# main.net
KiCad netlist of a schematic drawn in Altium Designer
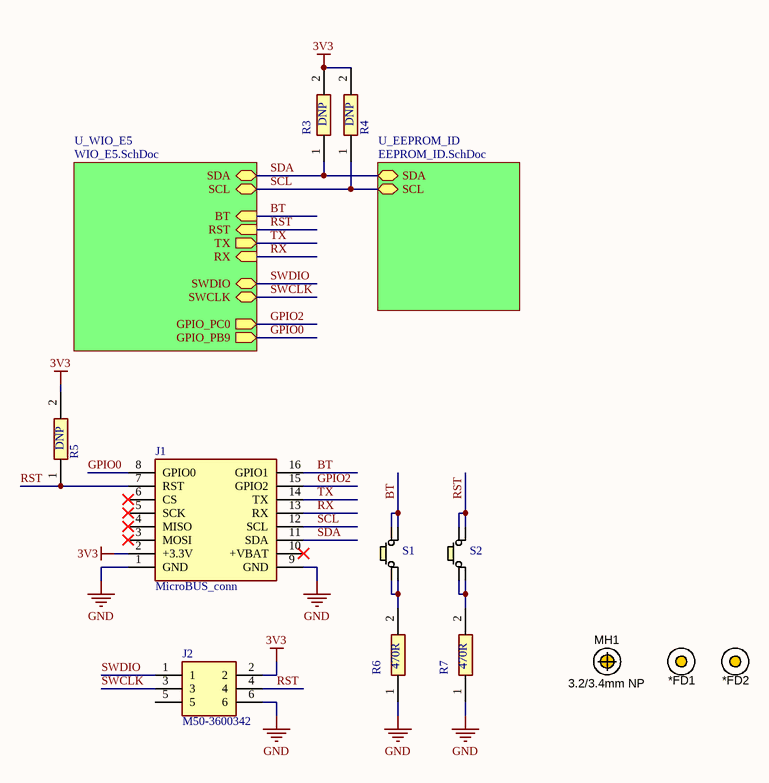
[diagram p0: main.SchDoc]

(export (version "E")
  (design (tool "Eeschema 10.0.6"))
  (components
    (comp (ref "*FD1")
      (value "FIDUCIAL")
      (footprint "IntLibGenerator:FIDUCIAL")
      (description "Fiducial")
      (fields
        (field (name "PARTNUMBER") "MCH_00028")
        (field (name "MANUFACTURER") "LE")
        (field (name "AUTOR") "Lukas Krahulec")
        (field (name "DESIGNER") "Lukas Krahulec")
        (field (name "LIBRARIAN") "Lukas Krahulec")
      )
      (libsource (lib "IntLibGenerator") (part "MCH_00028"))
    )
    (comp (ref "*FD2")
      (value "FIDUCIAL")
      (footprint "IntLibGenerator:FIDUCIAL")
      (description "Fiducial")
      (fields
        (field (name "PARTNUMBER") "MCH_00028")
        (field (name "MANUFACTURER") "LE")
        (field (name "AUTOR") "Lukas Krahulec")
        (field (name "DESIGNER") "Lukas Krahulec")
        (field (name "LIBRARIAN") "Lukas Krahulec")
      )
      (libsource (lib "IntLibGenerator") (part "MCH_00028"))
    )
    (comp (ref "J1")
      (value "MicroBUS_conn")
      (footprint "MicroBUS_header")
      (description "Connector")
      (fields
        (field (name "MANUFACTURER_PART_NUMBER") "M20-9730845")
        (field (name "MOUSER PART NUMBER") "855-M20-9730845")
      )
      (libsource (lib "SamacSys") (part "MicroBUS_conn"))
    )
    (comp (ref "J2")
      (value "M50-3600342")
      (footprint "SamacSys:HUSSP6W42P127_2X3_381X340X440P")
      (description "Connector")
      (fields (field (name "MOUSER PART NUMBER") "855-M50-3600342"))
      (libsource (lib "*") (part "M50-3600342"))
    )
    (comp (ref "MH1")
      (value "3.2/3.4mm NP")
      (footprint "TH_MH3.2/3.4NP")
      (description "(Mount Hole 3.2mm)")
      (fields
        (field (name "PARTNUMBER") "MCH_00037")
        (field (name "MANUFACTURER") "LE")
        (field (name "AUTOR") "Lukas Krahulec")
        (field (name "DESIGNER") "Lukas Krahulec")
        (field (name "LIBRARIAN") "Lukas Krahulec")
      )
      (libsource (lib "IntLibGenerator") (part "MCH_00037"))
    )
    (comp (ref "R3")
      (value "DNP")
      (footprint "SamacSys:RESC1005X35N")
      (description "Resistor")
      (fields (field (name "MANUFACTURER_PART_NUMBER") "RT0402FRE075K1L"))
      (libsource (lib "SamacSys") (part "RT0402FRE075K1L"))
    )
    (comp (ref "R4")
      (value "DNP")
      (footprint "SamacSys:RESC1005X35N")
      (description "Resistor")
      (fields (field (name "MANUFACTURER_PART_NUMBER") "RT0402FRE075K1L"))
      (libsource (lib "SamacSys") (part "RT0402FRE075K1L"))
    )
    (comp (ref "R5")
      (value "DNP")
      (footprint "SamacSys:RESC1005X35N")
      (description "Resistor")
      (fields (field (name "MANUFACTURER_PART_NUMBER") "RT0402FRE075K1L"))
      (libsource (lib "SamacSys") (part "RT0402FRE075K1L"))
    )
    (comp (ref "R6")
      (value "470R")
      (footprint "SamacSys:RESC1005X40N")
      (description "Resistor")
      (fields
        (field (name "MANUFACTURER_PART_NUMBER") "RC0402JR-07470RL")
        (field (name "MOUSER PART NUMBER") "603-RC0402JR-07470RL")
      )
      (libsource (lib "*") (part "RC0402JR-07470RL"))
    )
    (comp (ref "R7")
      (value "470R")
      (footprint "SamacSys:RESC1005X40N")
      (description "Resistor")
      (fields
        (field (name "MANUFACTURER_PART_NUMBER") "RC0402JR-07470RL")
        (field (name "MOUSER PART NUMBER") "603-RC0402JR-07470RL")
      )
      (libsource (lib "*") (part "RC0402JR-07470RL"))
    )
    (comp (ref "S1")
      (value "KMR731NG_LFS")
      (footprint "SamacSys:KMR731NGLFS")
      (description "Switch")
      (fields
        (field (name "MANUFACTURER_PART_NUMBER") "KMR731NG LFS")
        (field (name "MOUSER PART NUMBER") "611-KMR731NGLFS")
      )
      (libsource (lib "SamacSys") (part "KMR731NG_LFS"))
    )
    (comp (ref "S2")
      (value "KMR731NG_LFS")
      (footprint "SamacSys:KMR731NGLFS")
      (description "Switch")
      (fields
        (field (name "MANUFACTURER_PART_NUMBER") "KMR731NG LFS")
        (field (name "MOUSER PART NUMBER") "611-KMR731NGLFS")
      )
      (libsource (lib "SamacSys") (part "KMR731NG_LFS"))
    )
  )
  (nets
    (net (code "1") (name "/BT") (class "Default")
      (node (ref "J1") (pin "16") (pinfunction "GPIO1_16") (pintype "passive"))
      (node (ref "S1") (pin "3") (pinfunction "3_3") (pintype "passive"))
      (node (ref "S1") (pin "4") (pinfunction "4_4") (pintype "passive"))
    )
    (net (code "2") (name "/GPIO0") (class "Default")
      (node (ref "J1") (pin "8") (pinfunction "GPIO0_8") (pintype "passive"))
    )
    (net (code "3") (name "/GPIO2") (class "Default")
      (node (ref "J1") (pin "15") (pinfunction "GPIO2_15") (pintype "passive"))
    )
    (net (code "4") (name "/RST") (class "Default")
      (node (ref "J1") (pin "7") (pinfunction "RST_7") (pintype "passive"))
      (node (ref "J2") (pin "4") (pinfunction "4_4") (pintype "passive"))
      (node (ref "R5") (pin "1") (pinfunction "1_1") (pintype "passive"))
      (node (ref "S2") (pin "3") (pinfunction "3_3") (pintype "passive"))
      (node (ref "S2") (pin "4") (pinfunction "4_4") (pintype "passive"))
    )
    (net (code "5") (name "/RX") (class "Default")
      (node (ref "J1") (pin "13") (pinfunction "RX_13") (pintype "passive"))
    )
    (net (code "6") (name "/SCL") (class "Default")
      (node (ref "J1") (pin "12") (pinfunction "SCL_12") (pintype "passive"))
      (node (ref "R4") (pin "1") (pinfunction "1_1") (pintype "passive"))
    )
    (net (code "7") (name "/SDA") (class "Default")
      (node (ref "J1") (pin "11") (pinfunction "SDA_11") (pintype "passive"))
      (node (ref "R3") (pin "1") (pinfunction "1_1") (pintype "passive"))
    )
    (net (code "8") (name "/SWCLK") (class "Default")
      (node (ref "J2") (pin "3") (pinfunction "3_3") (pintype "passive"))
    )
    (net (code "9") (name "/SWDIO") (class "Default")
      (node (ref "J2") (pin "1") (pinfunction "1_1") (pintype "passive"))
    )
    (net (code "10") (name "/TX") (class "Default")
      (node (ref "J1") (pin "14") (pinfunction "TX_14") (pintype "passive"))
    )
    (net (code "11") (name "3V3") (class "Default")
      (node (ref "J1") (pin "2") (pinfunction "+3.3V_2") (pintype "passive"))
      (node (ref "J2") (pin "2") (pinfunction "2_2") (pintype "passive"))
      (node (ref "R3") (pin "2") (pinfunction "2_2") (pintype "passive"))
      (node (ref "R4") (pin "2") (pinfunction "2_2") (pintype "passive"))
      (node (ref "R5") (pin "2") (pinfunction "2_2") (pintype "passive"))
    )
    (net (code "12") (name "GND") (class "Default")
      (node (ref "J1") (pin "1") (pinfunction "GND_1") (pintype "passive"))
      (node (ref "J1") (pin "9") (pinfunction "GND_9") (pintype "passive"))
      (node (ref "J2") (pin "6") (pinfunction "6_6") (pintype "passive"))
      (node (ref "R6") (pin "1") (pinfunction "1_1") (pintype "passive"))
      (node (ref "R7") (pin "1") (pinfunction "1_1") (pintype "passive"))
    )
    (net (code "13") (name "Net-(R6-Pad2)") (class "Default")
      (node (ref "R6") (pin "2") (pinfunction "2_2") (pintype "passive"))
      (node (ref "S1") (pin "1") (pinfunction "1_1") (pintype "passive"))
      (node (ref "S1") (pin "2") (pinfunction "2_2") (pintype "passive"))
    )
    (net (code "14") (name "Net-(R7-Pad2)") (class "Default")
      (node (ref "R7") (pin "2") (pinfunction "2_2") (pintype "passive"))
      (node (ref "S2") (pin "1") (pinfunction "1_1") (pintype "passive"))
      (node (ref "S2") (pin "2") (pinfunction "2_2") (pintype "passive"))
    )
    (net (code "15") (name "unconnected-(*FD1-Pad1)") (class "Default")
      (node (ref "*FD1") (pin "1") (pinfunction "1_1") (pintype "passive"))
    )
    (net (code "16") (name "unconnected-(*FD2-Pad1)") (class "Default")
      (node (ref "*FD2") (pin "1") (pinfunction "1_1") (pintype "passive"))
    )
    (net (code "17") (name "unconnected-(J1-+VBAT-Pad10)") (class "Default")
      (node (ref "J1") (pin "10") (pinfunction "+VBAT_10") (pintype "passive+no_connect"))
    )
    (net (code "18") (name "unconnected-(J1-CS-Pad6)") (class "Default")
      (node (ref "J1") (pin "6") (pinfunction "CS_6") (pintype "passive+no_connect"))
    )
    (net (code "19") (name "unconnected-(J1-MISO-Pad4)") (class "Default")
      (node (ref "J1") (pin "4") (pinfunction "MISO_4") (pintype "passive+no_connect"))
    )
    (net (code "20") (name "unconnected-(J1-MOSI-Pad3)") (class "Default")
      (node (ref "J1") (pin "3") (pinfunction "MOSI_3") (pintype "passive+no_connect"))
    )
    (net (code "21") (name "unconnected-(J1-SCK-Pad5)") (class "Default")
      (node (ref "J1") (pin "5") (pinfunction "SCK_5") (pintype "passive+no_connect"))
    )
    (net (code "22") (name "unconnected-(J2-Pad5)") (class "Default")
      (node (ref "J2") (pin "5") (pinfunction "5_5") (pintype "passive"))
    )
  )
)
